# 2_lowpass_foreign_library.net
KiCad netlist of a schematic drawn in EAGLE
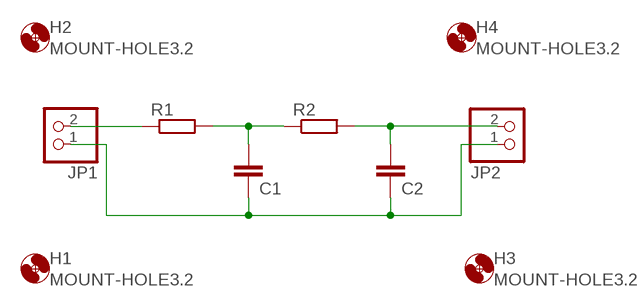
[diagram p0: schematic, sheet 1]

(export (version "E")
  (design (tool "Eeschema 10.0.6"))
  (components
    (comp (ref "C1")
      (value "C-EUC1206")
      (footprint "eagle-import:C1206")
      (libsource (lib "eagle-import") (part "C-EUC1206"))
    )
    (comp (ref "C2")
      (value "C-EUC1206")
      (footprint "eagle-import:C1206")
      (libsource (lib "eagle-import") (part "C-EUC1206"))
    )
    (comp (ref "H1")
      (value "MOUNT-HOLE3.2")
      (footprint "eagle-import:3,2")
      (libsource (lib "eagle-import") (part "MOUNT-HOLE3.2"))
    )
    (comp (ref "H2")
      (value "MOUNT-HOLE3.2")
      (footprint "eagle-import:3,2")
      (libsource (lib "eagle-import") (part "MOUNT-HOLE3.2"))
    )
    (comp (ref "H3")
      (value "MOUNT-HOLE3.2")
      (footprint "eagle-import:3,2")
      (libsource (lib "eagle-import") (part "MOUNT-HOLE3.2"))
    )
    (comp (ref "H4")
      (value "MOUNT-HOLE3.2")
      (footprint "eagle-import:3,2")
      (libsource (lib "eagle-import") (part "MOUNT-HOLE3.2"))
    )
    (comp (ref "JP1")
      (value "PINHD-1X2")
      (footprint "eagle-import:1X02")
      (libsource (lib "eagle-import") (part "PINHD-1X2"))
    )
    (comp (ref "JP2")
      (value "PINHD-1X2")
      (footprint "eagle-import:1X02")
      (libsource (lib "eagle-import") (part "PINHD-1X2"))
    )
    (comp (ref "R1")
      (value "R-EU_M1206")
      (footprint "eagle-import:M1206")
      (libsource (lib "eagle-import") (part "R-EU_M1206"))
    )
    (comp (ref "R2")
      (value "R-EU_M1206")
      (footprint "eagle-import:M1206")
      (libsource (lib "eagle-import") (part "R-EU_M1206"))
    )
  )
  (nets
    (net (code "1") (name "Net-(C1-Pad1)") (class "Default")
      (node (ref "C1") (pin "1") (pinfunction "1_1") (pintype "passive"))
      (node (ref "C2") (pin "1") (pinfunction "1_1") (pintype "passive"))
      (node (ref "JP1") (pin "1") (pinfunction "1_1") (pintype "passive"))
      (node (ref "JP2") (pin "1") (pinfunction "1_1") (pintype "passive"))
    )
    (net (code "2") (name "Net-(C1-Pad2)") (class "Default")
      (node (ref "C1") (pin "2") (pinfunction "2_2") (pintype "passive"))
      (node (ref "R1") (pin "2") (pinfunction "2_2") (pintype "passive"))
      (node (ref "R2") (pin "1") (pinfunction "1_1") (pintype "passive"))
    )
    (net (code "3") (name "Net-(C2-Pad2)") (class "Default")
      (node (ref "C2") (pin "2") (pinfunction "2_2") (pintype "passive"))
      (node (ref "JP2") (pin "2") (pinfunction "2_2") (pintype "passive"))
      (node (ref "R2") (pin "2") (pinfunction "2_2") (pintype "passive"))
    )
    (net (code "4") (name "Net-(JP1-Pad2)") (class "Default")
      (node (ref "JP1") (pin "2") (pinfunction "2_2") (pintype "passive"))
      (node (ref "R1") (pin "1") (pinfunction "1_1") (pintype "passive"))
    )
  )
)
